# Communications.net
KiCad netlist of a schematic drawn in Altium Designer
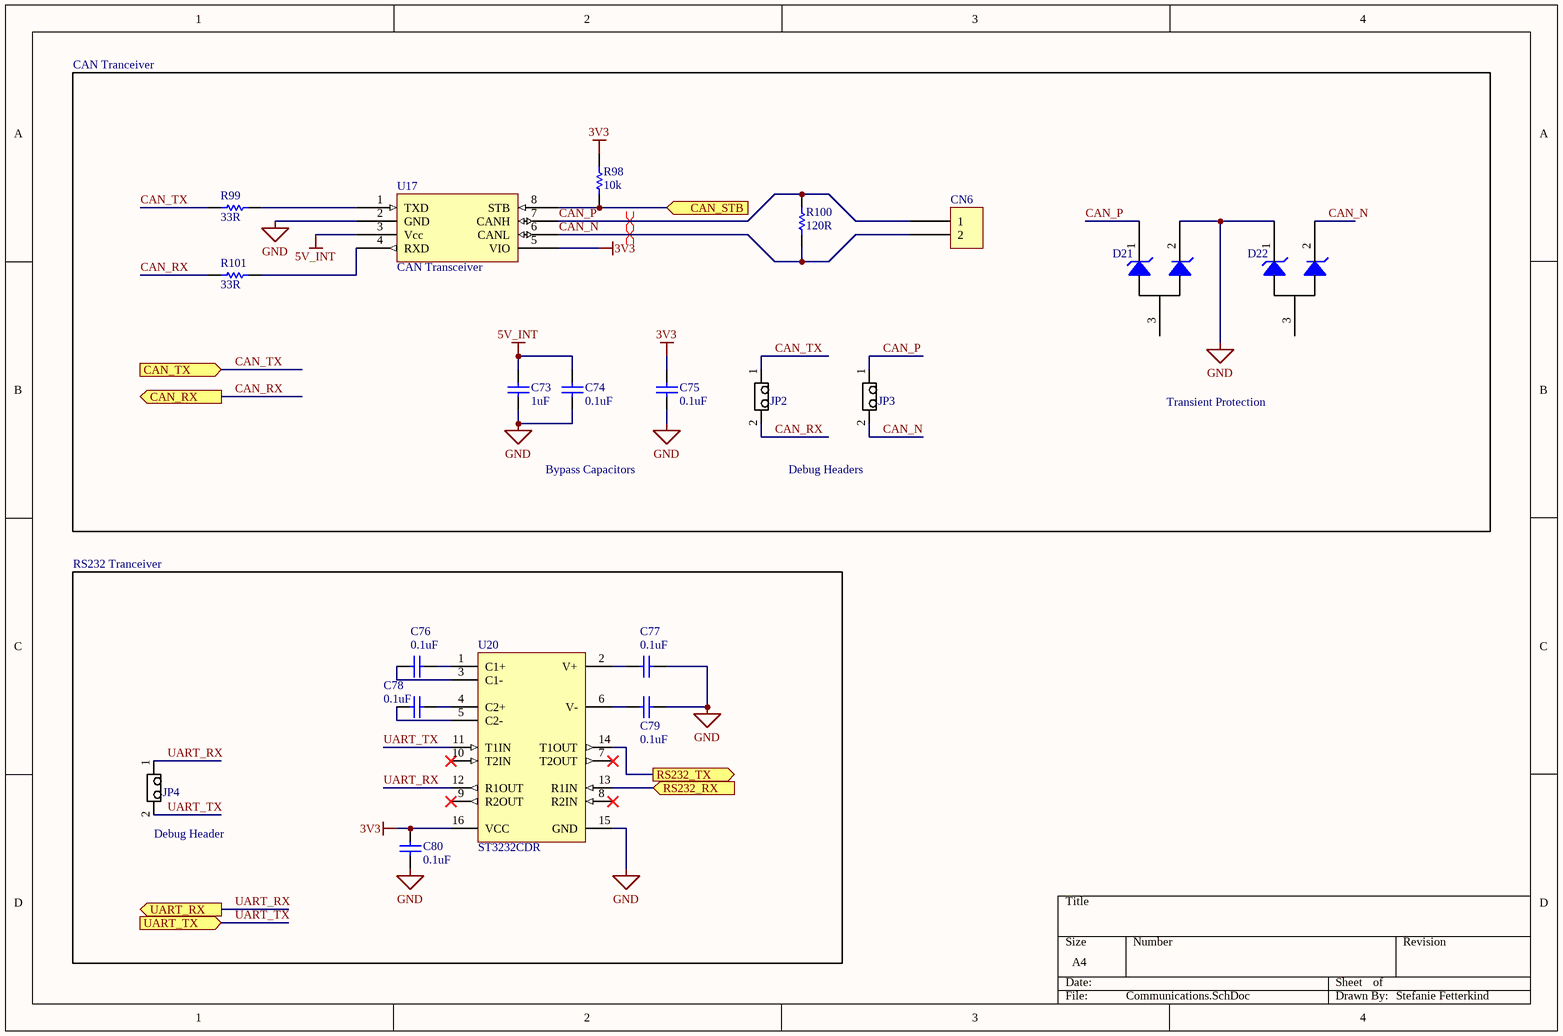
[diagram p0: Communications.SchDoc]

(export (version "E")
  (design (tool "Eeschema 10.0.6"))
  (components
    (comp (ref "C73")
      (value "CL21B105KBFNNNG")
      (footprint "0803 CAP")
      (description "SAMSUNG ELECTRO-MECHANICS - CL21B105KBFNNNG - MLCC CAPACITORS")
      (fields
        (field (name "TOLERANCE") "10%")
        (field (name "CAPACITANCE") "1uF")
        (field (name "VOLTAGE") "50V")
      )
      (libsource (lib "") (part "Symbol_1"))
    )
    (comp (ref "C74")
      (value "CL10B104JB8NNNC")
      (footprint "FP-CL10-0_1-IPC_A")
      (description "CAP CER 0.1UF 50V X7R 0603")
      (fields
        (field (name "TOLERANCE") "5%")
        (field (name "VOLTAGE") "50V")
        (field (name "CAPACITANCE") "0.1uF")
      )
      (libsource (lib "AUVIC") (part "CAP-NP-2"))
    )
    (comp (ref "C75")
      (value "CL10B104JB8NNNC")
      (footprint "FP-CL10-0_1-IPC_A")
      (description "CAP CER 0.1UF 50V X7R 0603")
      (fields
        (field (name "TOLERANCE") "5%")
        (field (name "VOLTAGE") "50V")
        (field (name "CAPACITANCE") "0.1uF")
      )
      (libsource (lib "AUVIC") (part "CAP-NP-2"))
    )
    (comp (ref "C76")
      (value "CL10B104JB8NNNC")
      (footprint "FP-CL10-0_1-IPC_A")
      (description "CAP CER 0.1UF 50V X7R 0603")
      (fields
        (field (name "TOLERANCE") "5%")
        (field (name "VOLTAGE") "50V")
        (field (name "CAPACITANCE") "0.1uF")
      )
      (libsource (lib "AUVIC") (part "CAP-NP-2"))
    )
    (comp (ref "C77")
      (value "CL10B104JB8NNNC")
      (footprint "FP-CL10-0_1-IPC_A")
      (description "CAP CER 0.1UF 50V X7R 0603")
      (fields
        (field (name "TOLERANCE") "5%")
        (field (name "VOLTAGE") "50V")
        (field (name "CAPACITANCE") "0.1uF")
      )
      (libsource (lib "AUVIC") (part "CAP-NP-2"))
    )
    (comp (ref "C78")
      (value "CL10B104JB8NNNC")
      (footprint "FP-CL10-0_1-IPC_A")
      (description "CAP CER 0.1UF 50V X7R 0603")
      (fields
        (field (name "TOLERANCE") "5%")
        (field (name "VOLTAGE") "50V")
        (field (name "CAPACITANCE") "0.1uF")
      )
      (libsource (lib "AUVIC") (part "CAP-NP-2"))
    )
    (comp (ref "C79")
      (value "CL10B104JB8NNNC")
      (footprint "FP-CL10-0_1-IPC_A")
      (description "CAP CER 0.1UF 50V X7R 0603")
      (fields
        (field (name "TOLERANCE") "5%")
        (field (name "VOLTAGE") "50V")
        (field (name "CAPACITANCE") "0.1uF")
      )
      (libsource (lib "AUVIC") (part "CAP-NP-2"))
    )
    (comp (ref "C80")
      (value "CL10B104JB8NNNC")
      (footprint "FP-CL10-0_1-IPC_A")
      (description "CAP CER 0.1UF 50V X7R 0603")
      (fields
        (field (name "TOLERANCE") "5%")
        (field (name "VOLTAGE") "50V")
        (field (name "CAPACITANCE") "0.1uF")
      )
      (libsource (lib "AUVIC") (part "CAP-NP-2"))
    )
    (comp (ref "CN6")
      (value "1x2 Shrouded Right Angle")
      (footprint "2X1 Female Header")
      (description "02 MTE HDR SRRA LATCH")
      (libsource (lib "AUVIC") (part "1x2 Shrouded Right Angle"))
    )
    (comp (ref "D21")
      (value "PESD36VS2UT,215")
      (footprint "SOT95P245X110-3N")
      (description "TVS DIODE 36V 60V SOT23")
      (fields (field (name "CREATED BY") "Miguel Manguerra"))
      (libsource (lib "AUVIC") (part "PESD36VS2UT,215"))
    )
    (comp (ref "D22")
      (value "PESD36VS2UT,215")
      (footprint "SOT95P245X110-3N")
      (description "TVS DIODE 36V 60V SOT23")
      (fields (field (name "CREATED BY") "Miguel Manguerra"))
      (libsource (lib "AUVIC") (part "PESD36VS2UT,215"))
    )
    (comp (ref "JP2")
      (value "1x2 Male Header")
      (footprint "2X1 Males Header")
      (fields (field (name "MADE BY") "Andy Bates"))
      (libsource (lib "AUVIC") (part "1x2 Male Header"))
    )
    (comp (ref "JP3")
      (value "1x2 Male Header")
      (footprint "2X1 Males Header")
      (fields (field (name "MADE BY") "Andy Bates"))
      (libsource (lib "AUVIC") (part "1x2 Male Header"))
    )
    (comp (ref "JP4")
      (value "1x2 Male Header")
      (footprint "2X1 Males Header")
      (fields (field (name "MADE BY") "Andy Bates"))
      (libsource (lib "AUVIC") (part "1x2 Male Header"))
    )
    (comp (ref "R98")
      (value "10k")
      (footprint "RESC1608N(0603\")")
      (description "10kR, 1%, 1/10W, 0603 SMD")
      (fields (field (name "MADE BY") "Ashwin Sira"))
      (libsource (lib "AUVIC") (part "Symbol"))
    )
    (comp (ref "R99")
      (value "RC0603FR-0733RL")
      (footprint "RESC1608X55X25ML10T15")
      (description "Res Thick Film 0603 33 Ohm 1% 1/10W +/-100ppm/ßC Molded SMD Paper T/R")
      (fields (field (name "RESISTANCE") "33R") (field (name "TOLERANCE") "1%"))
      (libsource (lib "AUVIC") (part "RES-2"))
    )
    (comp (ref "R100")
      (value "RC0603FR-07120RL")
      (footprint "RESC1608X55X25ML10T15")
      (description "Res Thick Film 0603 120 Ohm 1% 0.1W(1/10W) ±100ppm/C Epoxy SMD T/R")
      (fields (field (name "RESISTANCE") "120R") (field (name "TOLERANCE") "1%"))
      (libsource (lib "AUVIC") (part "RES-2"))
    )
    (comp (ref "R101")
      (value "RC0603FR-0733RL")
      (footprint "RESC1608X55X25ML10T15")
      (description "Res Thick Film 0603 33 Ohm 1% 1/10W +/-100ppm/ßC Molded SMD Paper T/R")
      (fields (field (name "RESISTANCE") "33R") (field (name "TOLERANCE") "1%"))
      (libsource (lib "AUVIC") (part "RES-2"))
    )
    (comp (ref "U17")
      (value "CAN Transceiver")
      (footprint "8-SOIC")
      (description "1/1 Transceiver Half CANbus 8-SO")
      (libsource (lib "AUVIC") (part "CAN Transceiver"))
    )
    (comp (ref "U20")
      (value "ST3232CDR")
      (footprint "STM-SO-16_M")
      (description "Dual Transmitter/Receiver RS-232 16-Pin SO T/R")
      (libsource (lib "AUVIC") (part "STM-ST3232-SO-16"))
    )
  )
  (nets
    (net (code "1") (name "/CAN_N") (class "Default")
      (node (ref "CN6") (pin "2") (pinfunction "2_2") (pintype "passive"))
      (node (ref "D22") (pin "2") (pinfunction "Cathode_2_2") (pintype "passive"))
      (node (ref "JP3") (pin "2") (pinfunction "2_2") (pintype "passive"))
      (node (ref "R100") (pin "1") (pinfunction "1_1") (pintype "passive"))
      (node (ref "U17") (pin "6") (pinfunction "CANL_6") (pintype "bidirectional"))
    )
    (net (code "2") (name "/CAN_P") (class "Default")
      (node (ref "CN6") (pin "1") (pinfunction "1_1") (pintype "passive"))
      (node (ref "D21") (pin "1") (pinfunction "Cathode_1_1") (pintype "passive"))
      (node (ref "JP3") (pin "1") (pinfunction "1_1") (pintype "passive"))
      (node (ref "R100") (pin "2") (pinfunction "2_2") (pintype "passive"))
      (node (ref "U17") (pin "7") (pinfunction "CANH_7") (pintype "bidirectional"))
    )
    (net (code "3") (name "/CAN_RX") (class "Default")
      (node (ref "JP2") (pin "2") (pinfunction "2_2") (pintype "passive"))
      (node (ref "R101") (pin "2") (pinfunction "2_2") (pintype "passive"))
    )
    (net (code "4") (name "/CAN_STB") (class "Default")
      (node (ref "R98") (pin "1") (pinfunction "1_1") (pintype "passive"))
      (node (ref "U17") (pin "8") (pinfunction "STB_8") (pintype "input"))
    )
    (net (code "5") (name "/CAN_TX") (class "Default")
      (node (ref "JP2") (pin "1") (pinfunction "1_1") (pintype "passive"))
      (node (ref "R99") (pin "2") (pinfunction "2_2") (pintype "passive"))
    )
    (net (code "6") (name "/RS232_RX") (class "Default")
      (node (ref "U20") (pin "13") (pinfunction "R1IN_13") (pintype "input"))
    )
    (net (code "7") (name "/RS232_TX") (class "Default")
      (node (ref "U20") (pin "14") (pinfunction "T1OUT_14") (pintype "output"))
    )
    (net (code "8") (name "/UART_RX") (class "Default")
      (node (ref "JP4") (pin "1") (pinfunction "1_1") (pintype "passive"))
      (node (ref "U20") (pin "12") (pinfunction "R1OUT_12") (pintype "output"))
    )
    (net (code "9") (name "/UART_TX") (class "Default")
      (node (ref "JP4") (pin "2") (pinfunction "2_2") (pintype "passive"))
      (node (ref "U20") (pin "11") (pinfunction "T1IN_11") (pintype "input"))
    )
    (net (code "10") (name "3V3") (class "Default")
      (node (ref "C75") (pin "1") (pinfunction "1_1") (pintype "passive"))
      (node (ref "C80") (pin "2") (pinfunction "2_2") (pintype "passive"))
      (node (ref "R98") (pin "2") (pinfunction "2_2") (pintype "passive"))
      (node (ref "U17") (pin "5") (pinfunction "VIO_5") (pintype "passive"))
      (node (ref "U20") (pin "16") (pinfunction "VCC_16") (pintype "power_in"))
    )
    (net (code "11") (name "5V_INT") (class "Default")
      (node (ref "C73") (pin "1") (pinfunction "1_1") (pintype "passive"))
      (node (ref "C74") (pin "1") (pinfunction "1_1") (pintype "passive"))
      (node (ref "U17") (pin "3") (pinfunction "Vcc_3") (pintype "power_in"))
    )
    (net (code "12") (name "GND") (class "Default")
      (node (ref "C73") (pin "2") (pinfunction "2_2") (pintype "passive"))
      (node (ref "C74") (pin "2") (pinfunction "2_2") (pintype "passive"))
      (node (ref "C75") (pin "2") (pinfunction "2_2") (pintype "passive"))
      (node (ref "C77") (pin "2") (pinfunction "2_2") (pintype "passive"))
      (node (ref "C79") (pin "2") (pinfunction "2_2") (pintype "passive"))
      (node (ref "C80") (pin "1") (pinfunction "1_1") (pintype "passive"))
      (node (ref "D21") (pin "2") (pinfunction "Cathode_2_2") (pintype "passive"))
      (node (ref "D22") (pin "1") (pinfunction "Cathode_1_1") (pintype "passive"))
      (node (ref "U17") (pin "2") (pinfunction "GND_2") (pintype "power_in"))
      (node (ref "U20") (pin "15") (pinfunction "GND_15") (pintype "power_in"))
    )
    (net (code "13") (name "Net-(U17-RXD)") (class "Default")
      (node (ref "R101") (pin "1") (pinfunction "1_1") (pintype "passive"))
      (node (ref "U17") (pin "4") (pinfunction "RXD_4") (pintype "output"))
    )
    (net (code "14") (name "Net-(U17-TXD)") (class "Default")
      (node (ref "R99") (pin "1") (pinfunction "1_1") (pintype "passive"))
      (node (ref "U17") (pin "1") (pinfunction "TXD_1") (pintype "input"))
    )
    (net (code "15") (name "Net-(U20-C1+)") (class "Default")
      (node (ref "C76") (pin "2") (pinfunction "2_2") (pintype "passive"))
      (node (ref "U20") (pin "1") (pinfunction "C1+_1") (pintype "passive"))
    )
    (net (code "16") (name "Net-(U20-C1-)") (class "Default")
      (node (ref "C76") (pin "1") (pinfunction "1_1") (pintype "passive"))
      (node (ref "U20") (pin "3") (pinfunction "C1-_3") (pintype "passive"))
    )
    (net (code "17") (name "Net-(U20-C2+)") (class "Default")
      (node (ref "C78") (pin "2") (pinfunction "2_2") (pintype "passive"))
      (node (ref "U20") (pin "4") (pinfunction "C2+_4") (pintype "passive"))
    )
    (net (code "18") (name "Net-(U20-C2-)") (class "Default")
      (node (ref "C78") (pin "1") (pinfunction "1_1") (pintype "passive"))
      (node (ref "U20") (pin "5") (pinfunction "C2-_5") (pintype "passive"))
    )
    (net (code "19") (name "Net-(U20-V+)") (class "Default")
      (node (ref "C77") (pin "1") (pinfunction "1_1") (pintype "passive"))
      (node (ref "U20") (pin "2") (pinfunction "V+_2") (pintype "power_in"))
    )
    (net (code "20") (name "Net-(U20-V-)") (class "Default")
      (node (ref "C79") (pin "1") (pinfunction "1_1") (pintype "passive"))
      (node (ref "U20") (pin "6") (pinfunction "V-_6") (pintype "power_in"))
    )
    (net (code "21") (name "unconnected-(D21-Common_Anode-Pad3)") (class "Default")
      (node (ref "D21") (pin "3") (pinfunction "Common_Anode_3") (pintype "passive"))
    )
    (net (code "22") (name "unconnected-(D22-Common_Anode-Pad3)") (class "Default")
      (node (ref "D22") (pin "3") (pinfunction "Common_Anode_3") (pintype "passive"))
    )
    (net (code "23") (name "unconnected-(U20-R2IN-Pad8)") (class "Default")
      (node (ref "U20") (pin "8") (pinfunction "R2IN_8") (pintype "input+no_connect"))
    )
    (net (code "24") (name "unconnected-(U20-R2OUT-Pad9)") (class "Default")
      (node (ref "U20") (pin "9") (pinfunction "R2OUT_9") (pintype "output+no_connect"))
    )
    (net (code "25") (name "unconnected-(U20-T2IN-Pad10)") (class "Default")
      (node (ref "U20") (pin "10") (pinfunction "T2IN_10") (pintype "input+no_connect"))
    )
    (net (code "26") (name "unconnected-(U20-T2OUT-Pad7)") (class "Default")
      (node (ref "U20") (pin "7") (pinfunction "T2OUT_7") (pintype "output+no_connect"))
    )
  )
)
